# FSR_Input_LM358.net
KiCad netlist of a schematic drawn in EAGLE
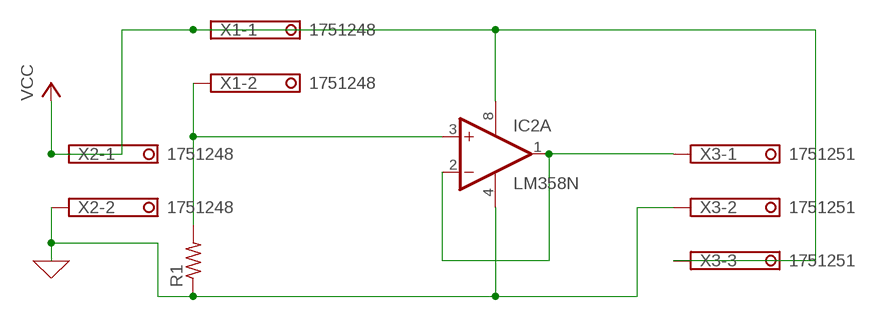
[diagram p0: schematic, sheet 1]

(export (version "E")
  (design (tool "Eeschema 10.0.6"))
  (components
    (comp (ref "IC2")
      (value "LM358N")
      (footprint "eagle-import:DIL08")
      (libsource (lib "eagle-import") (part "LM358N"))
    )
    (comp (ref "R1")
      (value "R-US_0204/5")
      (footprint "eagle-import:0204_5")
      (libsource (lib "eagle-import") (part "R-US_0204/5"))
    )
    (comp (ref "X1")
      (value "1751248")
      (footprint "eagle-import:1751248")
      (libsource (lib "eagle-import") (part "1751248"))
    )
    (comp (ref "X2")
      (value "1751248")
      (footprint "eagle-import:1751248")
      (libsource (lib "eagle-import") (part "1751248"))
    )
    (comp (ref "X3")
      (value "1751251")
      (footprint "eagle-import:1751251")
      (libsource (lib "eagle-import") (part "1751251"))
    )
  )
  (nets
    (net (code "1") (name "GND") (class "Default")
      (node (ref "IC2") (pin "4") (pinfunction "V-_4") (pintype "power_in"))
      (node (ref "R1") (pin "1") (pinfunction "1_1") (pintype "passive"))
      (node (ref "X2") (pin "2") (pinfunction "K_2") (pintype "passive"))
      (node (ref "X3") (pin "2") (pinfunction "K_2") (pintype "passive"))
    )
    (net (code "2") (name "Net-(IC2A-+IN)") (class "Default")
      (node (ref "IC2") (pin "3") (pinfunction "+IN_3") (pintype "input"))
      (node (ref "R1") (pin "2") (pinfunction "2_2") (pintype "passive"))
      (node (ref "X1") (pin "2") (pinfunction "K_2") (pintype "passive"))
    )
    (net (code "3") (name "Net-(IC2A--IN)") (class "Default")
      (node (ref "IC2") (pin "1") (pinfunction "OUT_1") (pintype "output"))
      (node (ref "IC2") (pin "2") (pinfunction "-IN_2") (pintype "input"))
      (node (ref "X3") (pin "1") (pinfunction "K_1") (pintype "passive"))
    )
    (net (code "4") (name "VCC") (class "Default")
      (node (ref "IC2") (pin "8") (pinfunction "V+_8") (pintype "power_in"))
      (node (ref "X1") (pin "1") (pinfunction "K_1") (pintype "passive"))
      (node (ref "X2") (pin "1") (pinfunction "K_1") (pintype "passive"))
      (node (ref "X3") (pin "3") (pinfunction "K_3") (pintype "passive"))
    )
  )
)
